# w12-reflect.net
KiCad netlist of a schematic drawn in EAGLE
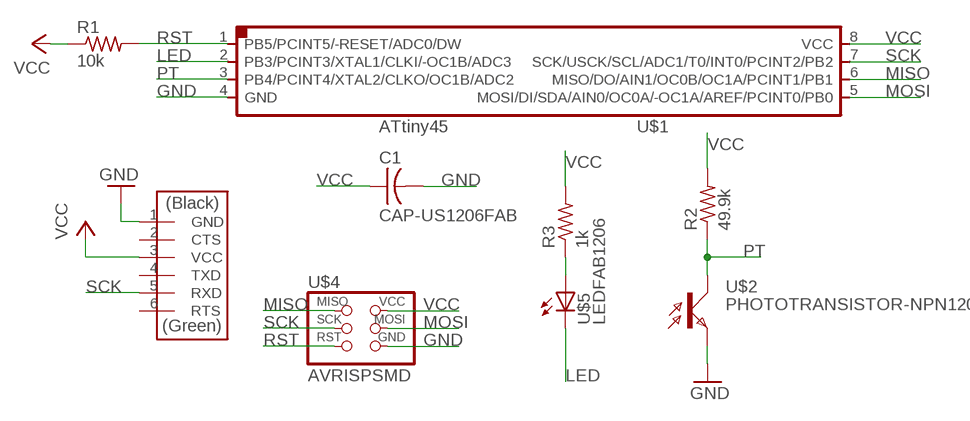
[diagram p0: schematic, sheet 1]

(export (version "E")
  (design (tool "Eeschema 10.0.6"))
  (components
    (comp (ref "C1")
      (value "CAP-US1206FAB")
      (footprint "eagle-import:C1206FAB")
      (libsource (lib "eagle-import") (part "CAP-US1206FAB"))
    )
    (comp (ref "R1")
      (value "10k")
      (footprint "eagle-import:R1206FAB")
      (libsource (lib "eagle-import") (part "RES-US1206FAB"))
    )
    (comp (ref "R2")
      (value "49.9k")
      (footprint "eagle-import:R1206FAB")
      (libsource (lib "eagle-import") (part "RES-US1206FAB"))
    )
    (comp (ref "R3")
      (value "1k")
      (footprint "eagle-import:R1206FAB")
      (libsource (lib "eagle-import") (part "RES-US1206FAB"))
    )
    (comp (ref "U$1")
      (value "ATTINY45SI")
      (footprint "eagle-import:SOIC8")
      (libsource (lib "eagle-import") (part "ATTINY45SI"))
    )
    (comp (ref "U$2")
      (value "PHOTOTRANSISTOR-NPN1206")
      (footprint "eagle-import:OP1206")
      (libsource (lib "eagle-import") (part "PHOTOTRANSISTOR-NPN1206"))
    )
    (comp (ref "U$3")
      (value "FTDI-SMD-HEADER")
      (footprint "eagle-import:1X06SMD")
      (libsource (lib "eagle-import") (part "FTDI-SMD-HEADER"))
    )
    (comp (ref "U$4")
      (value "AVRISPSMD")
      (footprint "eagle-import:2X03SMD")
      (libsource (lib "eagle-import") (part "AVRISPSMD"))
    )
    (comp (ref "U$5")
      (value "LEDFAB1206")
      (footprint "eagle-import:LED1206FAB")
      (libsource (lib "eagle-import") (part "LEDFAB1206"))
    )
  )
  (nets
    (net (code "1") (name "/LED") (class "Default")
      (node (ref "U$1") (pin "2") (pinfunction "PB3/PCINT3/XTAL1/CLKI/-OC1B/ADC3_2") (pintype "bidirectional"))
      (node (ref "U$5") (pin "2") (pinfunction "C_2") (pintype "passive"))
    )
    (net (code "2") (name "/MISO") (class "Default")
      (node (ref "U$1") (pin "6") (pinfunction "MISO/DO/AIN1/OC0B/OC1A/PCINT1/PB1_6") (pintype "bidirectional"))
      (node (ref "U$4") (pin "1") (pinfunction "MISO_1") (pintype "passive"))
    )
    (net (code "3") (name "/MOSI") (class "Default")
      (node (ref "U$1") (pin "5") (pinfunction "MOSI/DI/SDA/AIN0/OC0A/-OC1A/AREF/PCINT0/PB0_5") (pintype "bidirectional"))
      (node (ref "U$4") (pin "4") (pinfunction "MOSI_4") (pintype "passive"))
    )
    (net (code "4") (name "/PT") (class "Default")
      (node (ref "R2") (pin "1") (pinfunction "1_1") (pintype "passive"))
      (node (ref "U$1") (pin "3") (pinfunction "PB4/PCINT4/XTAL2/CLKO/OC1B/ADC2_3") (pintype "bidirectional"))
      (node (ref "U$2") (pin "COLLECTOR") (pinfunction "C_COLLECTOR") (pintype "passive"))
    )
    (net (code "5") (name "/RST") (class "Default")
      (node (ref "R1") (pin "2") (pinfunction "2_2") (pintype "passive"))
      (node (ref "U$1") (pin "1") (pinfunction "PB5/PCINT5/-RESET/ADC0/DW_1") (pintype "bidirectional"))
      (node (ref "U$4") (pin "5") (pinfunction "RST_5") (pintype "passive"))
    )
    (net (code "6") (name "/SCK") (class "Default")
      (node (ref "U$1") (pin "7") (pinfunction "SCK/USCK/SCL/ADC1/T0/INT0/PCINT2/PB2_7") (pintype "bidirectional"))
      (node (ref "U$3") (pin "5") (pinfunction "RXD_5") (pintype "bidirectional"))
      (node (ref "U$4") (pin "3") (pinfunction "SCK_3") (pintype "passive"))
    )
    (net (code "7") (name "GND") (class "Default")
      (node (ref "C1") (pin "2") (pinfunction "2_2") (pintype "passive"))
      (node (ref "U$1") (pin "4") (pinfunction "GND_4") (pintype "bidirectional"))
      (node (ref "U$2") (pin "EMITTER") (pinfunction "E_EMITTER") (pintype "passive"))
      (node (ref "U$3") (pin "1") (pinfunction "GND_1") (pintype "bidirectional"))
      (node (ref "U$4") (pin "6") (pinfunction "GND_6") (pintype "passive"))
    )
    (net (code "8") (name "Net-(U$5-A)") (class "Default")
      (node (ref "R3") (pin "1") (pinfunction "1_1") (pintype "passive"))
      (node (ref "U$5") (pin "1") (pinfunction "A_1") (pintype "passive"))
    )
    (net (code "9") (name "VCC") (class "Default")
      (node (ref "C1") (pin "1") (pinfunction "1_1") (pintype "passive"))
      (node (ref "R1") (pin "1") (pinfunction "1_1") (pintype "passive"))
      (node (ref "R2") (pin "2") (pinfunction "2_2") (pintype "passive"))
      (node (ref "R3") (pin "2") (pinfunction "2_2") (pintype "passive"))
      (node (ref "U$1") (pin "8") (pinfunction "VCC_8") (pintype "bidirectional"))
      (node (ref "U$3") (pin "3") (pinfunction "VCC_3") (pintype "bidirectional"))
      (node (ref "U$4") (pin "2") (pinfunction "VCC_2") (pintype "passive"))
    )
    (net (code "10") (name "unconnected-(U$3-CTS-Pad2)") (class "Default")
      (node (ref "U$3") (pin "2") (pinfunction "CTS_2") (pintype "bidirectional"))
    )
    (net (code "11") (name "unconnected-(U$3-RTS-Pad6)") (class "Default")
      (node (ref "U$3") (pin "6") (pinfunction "RTS_6") (pintype "bidirectional"))
    )
    (net (code "12") (name "unconnected-(U$3-TXD-Pad4)") (class "Default")
      (node (ref "U$3") (pin "4") (pinfunction "TXD_4") (pintype "bidirectional"))
    )
  )
)
